# esp32-4-channel.net
KiCad netlist of a schematic drawn in EasyEDA
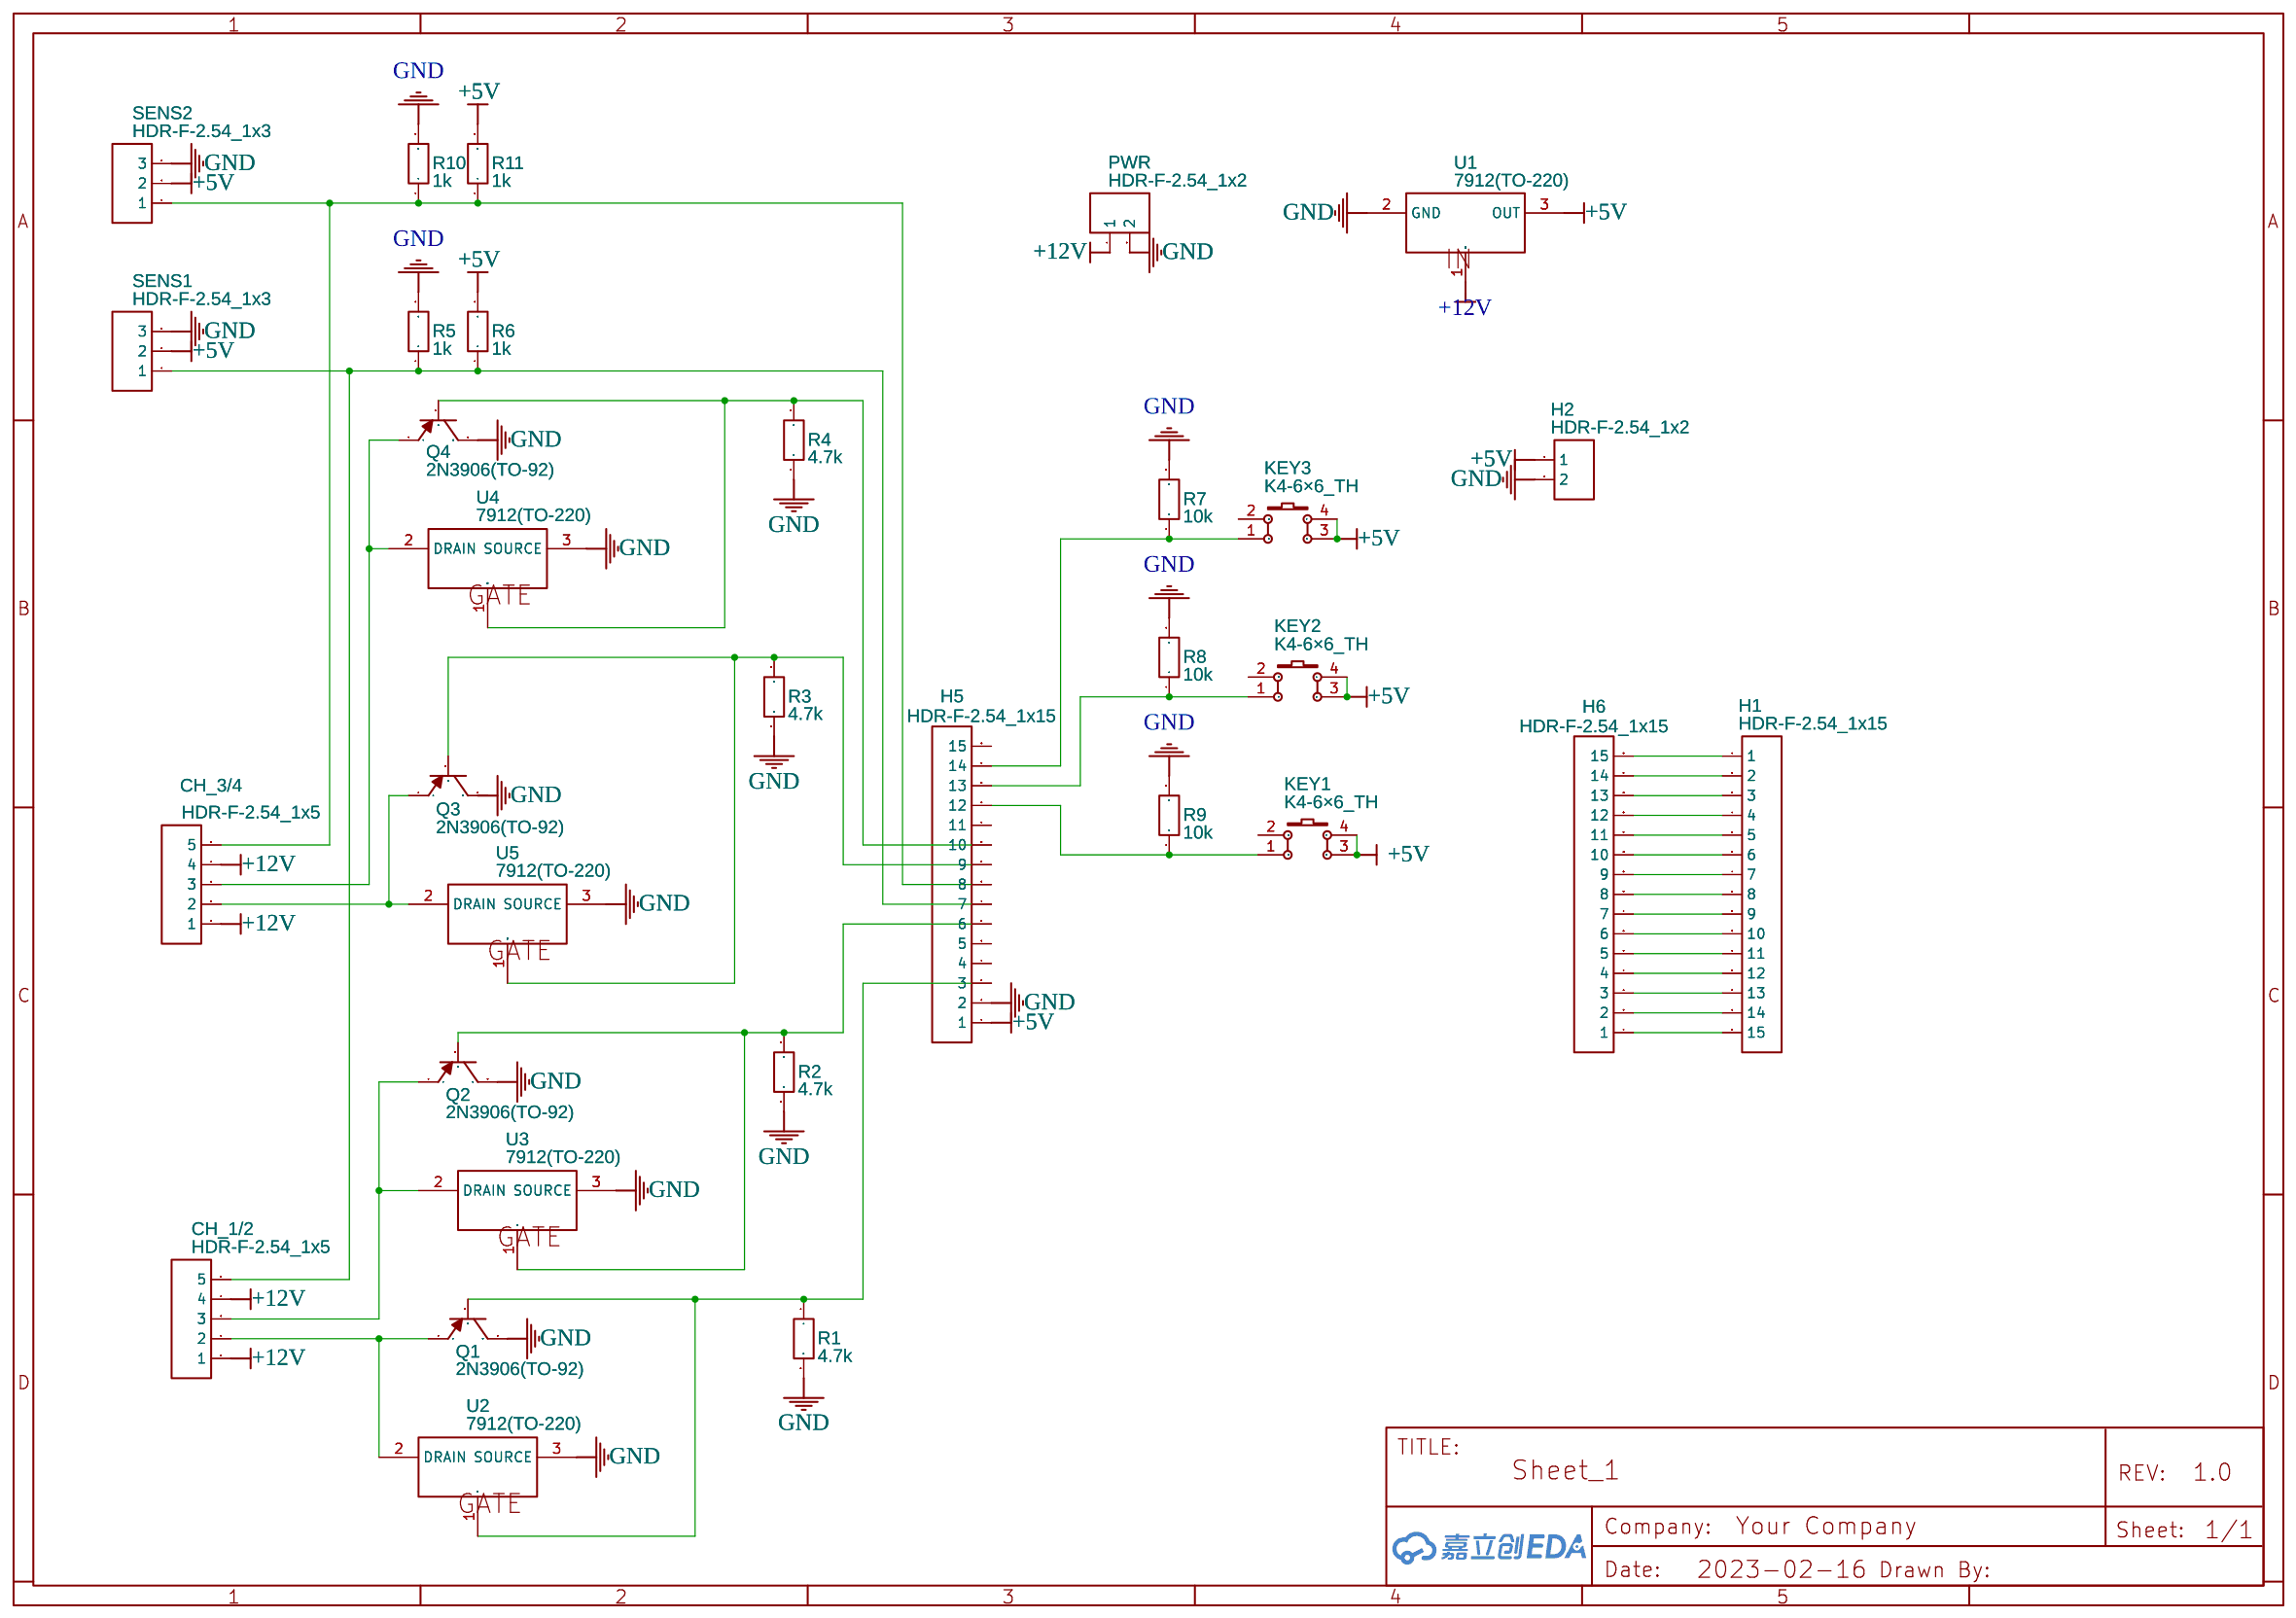
[diagram p0: schematic sheet]

(export (version "E")
  (design (tool "Eeschema 10.0.6"))
  (components
    (comp (ref "CH_1/2")
      (value "HDR-F-2.54_1x5")
      (fields (field (name "BOM_Supplier Part") "C50950"))
      (libsource (lib "") (part "HDR-F-2.54_1x5_1"))
    )
    (comp (ref "CH_3/4")
      (value "HDR-F-2.54_1x5")
      (fields (field (name "BOM_Supplier Part") "C50950"))
      (libsource (lib "") (part "HDR-F-2.54_1x5"))
    )
    (comp (ref "H1")
      (value "HDR-F-2.54_1x15")
      (fields (field (name "BOM_Supplier Part") "C124408"))
      (libsource (lib "") (part "HDR-F-2.54_1x15_1"))
    )
    (comp (ref "H2")
      (value "HDR-F-2.54_1x2")
      (fields (field (name "BOM_Supplier Part") "C49661"))
      (libsource (lib "") (part "HDR-F-2.54_1x2_1"))
    )
    (comp (ref "H5")
      (value "HDR-F-2.54_1x15")
      (fields (field (name "BOM_Supplier Part") "C124408"))
      (libsource (lib "") (part "HDR-F-2.54_1x15"))
    )
    (comp (ref "H6")
      (value "HDR-F-2.54_1x15")
      (fields (field (name "BOM_Supplier Part") "C124408"))
      (libsource (lib "") (part "HDR-F-2.54_1x15"))
    )
    (comp (ref "KEY1")
      (value "K4-6×6_TH")
      (fields
        (field (name "BOM_Manufacturer Part") "K2-1102DP-E4SW-04")
        (field (name "BOM_Supplier Part") "C136684")
      )
      (libsource (lib "") (part "K4-6×6_TH"))
    )
    (comp (ref "KEY2")
      (value "K4-6×6_TH")
      (fields
        (field (name "BOM_Manufacturer Part") "K2-1102DP-E4SW-04")
        (field (name "BOM_Supplier Part") "C136684")
      )
      (libsource (lib "") (part "K4-6×6_TH"))
    )
    (comp (ref "KEY3")
      (value "K4-6×6_TH")
      (fields
        (field (name "BOM_Manufacturer Part") "K2-1102DP-E4SW-04")
        (field (name "BOM_Supplier Part") "C136684")
      )
      (libsource (lib "") (part "K4-6×6_TH"))
    )
    (comp (ref "PWR")
      (value "HDR-F-2.54_1x2")
      (fields (field (name "BOM_Supplier Part") "C49661"))
      (libsource (lib "") (part "HDR-F-2.54_1x2"))
    )
    (comp (ref "Q1")
      (value "2N3906(TO-92)")
      (fields (field (name "BOM_Manufacturer Part") "2N3906") (field (name "BOM_Supplier Part") "C9809"))
      (libsource (lib "") (part "2N3906(TO-92)"))
    )
    (comp (ref "Q2")
      (value "2N3906(TO-92)")
      (fields (field (name "BOM_Manufacturer Part") "2N3906") (field (name "BOM_Supplier Part") "C9809"))
      (libsource (lib "") (part "2N3906(TO-92)"))
    )
    (comp (ref "Q3")
      (value "2N3906(TO-92)")
      (fields (field (name "BOM_Manufacturer Part") "2N3906") (field (name "BOM_Supplier Part") "C9809"))
      (libsource (lib "") (part "2N3906(TO-92)"))
    )
    (comp (ref "Q4")
      (value "2N3906(TO-92)")
      (fields (field (name "BOM_Manufacturer Part") "2N3906") (field (name "BOM_Supplier Part") "C9809"))
      (libsource (lib "") (part "2N3906(TO-92)"))
    )
    (comp (ref "R1") (value "4.7k") (libsource (lib "") (part "R_AXIAL-0.3_EU_1")))
    (comp (ref "R2") (value "4.7k") (libsource (lib "") (part "R_AXIAL-0.3_EU")))
    (comp (ref "R3") (value "4.7k") (libsource (lib "") (part "R_AXIAL-0.3_EU")))
    (comp (ref "R4") (value "4.7k") (libsource (lib "") (part "R_AXIAL-0.3_EU")))
    (comp (ref "R5") (value "1k") (libsource (lib "") (part "R_AXIAL-0.3_EU")))
    (comp (ref "R6") (value "1k") (libsource (lib "") (part "R_AXIAL-0.3_EU")))
    (comp (ref "R7") (value "10k") (libsource (lib "") (part "R_AXIAL-0.3_EU")))
    (comp (ref "R8") (value "10k") (libsource (lib "") (part "R_AXIAL-0.3_EU")))
    (comp (ref "R9") (value "10k") (libsource (lib "") (part "R_AXIAL-0.3_EU")))
    (comp (ref "R10") (value "1k") (libsource (lib "") (part "R_AXIAL-0.3_EU")))
    (comp (ref "R11") (value "1k") (libsource (lib "") (part "R_AXIAL-0.3_EU")))
    (comp (ref "SENS1")
      (value "HDR-F-2.54_1x3")
      (fields (field (name "BOM_Supplier Part") "C146690"))
      (libsource (lib "") (part "HDR-F-2.54_1x3"))
    )
    (comp (ref "SENS2")
      (value "HDR-F-2.54_1x3")
      (fields (field (name "BOM_Supplier Part") "C146690"))
      (libsource (lib "") (part "HDR-F-2.54_1x3"))
    )
    (comp (ref "U1")
      (value "7912(TO-220)")
      (fields (field (name "BOM_Manufacturer Part") "L7912CV-DG") (field (name "BOM_Supplier Part") "C3797"))
      (libsource (lib "") (part "7912(TO-220)_1"))
    )
    (comp (ref "U2")
      (value "7912(TO-220)")
      (fields (field (name "BOM_Manufacturer Part") "L7912CV-DG") (field (name "BOM_Supplier Part") "C3797"))
      (libsource (lib "") (part "7912(TO-220)"))
    )
    (comp (ref "U3")
      (value "7912(TO-220)")
      (fields (field (name "BOM_Manufacturer Part") "L7912CV-DG") (field (name "BOM_Supplier Part") "C3797"))
      (libsource (lib "") (part "7912(TO-220)"))
    )
    (comp (ref "U4")
      (value "7912(TO-220)")
      (fields (field (name "BOM_Manufacturer Part") "L7912CV-DG") (field (name "BOM_Supplier Part") "C3797"))
      (libsource (lib "") (part "7912(TO-220)"))
    )
    (comp (ref "U5")
      (value "7912(TO-220)")
      (fields (field (name "BOM_Manufacturer Part") "L7912CV-DG") (field (name "BOM_Supplier Part") "C3797"))
      (libsource (lib "") (part "7912(TO-220)"))
    )
  )
  (nets
    (net (code "1") (name "+5V") (class "Default")
      (node (ref "H2") (pin "1") (pinfunction "1_1") (pintype "input"))
      (node (ref "H5") (pin "1") (pinfunction "1_1") (pintype "unspecified"))
      (node (ref "KEY1") (pin "3") (pinfunction "3_3") (pintype "unspecified"))
      (node (ref "KEY1") (pin "4") (pinfunction "4_4") (pintype "unspecified"))
      (node (ref "KEY2") (pin "3") (pinfunction "3_3") (pintype "unspecified"))
      (node (ref "KEY2") (pin "4") (pinfunction "4_4") (pintype "unspecified"))
      (node (ref "KEY3") (pin "3") (pinfunction "3_3") (pintype "unspecified"))
      (node (ref "KEY3") (pin "4") (pinfunction "4_4") (pintype "unspecified"))
      (node (ref "R11") (pin "2") (pinfunction "2_2") (pintype "unspecified"))
      (node (ref "R6") (pin "2") (pinfunction "2_2") (pintype "unspecified"))
      (node (ref "SENS1") (pin "2") (pinfunction "2_2") (pintype "input"))
      (node (ref "SENS2") (pin "2") (pinfunction "2_2") (pintype "input"))
      (node (ref "U1") (pin "3") (pinfunction "OUT_3") (pintype "passive"))
    )
    (net (code "2") (name "+12V") (class "Default")
      (node (ref "CH_1/2") (pin "1") (pinfunction "1_1") (pintype "unspecified"))
      (node (ref "CH_1/2") (pin "4") (pinfunction "4_4") (pintype "unspecified"))
      (node (ref "CH_3/4") (pin "1") (pinfunction "1_1") (pintype "unspecified"))
      (node (ref "CH_3/4") (pin "4") (pinfunction "4_4") (pintype "unspecified"))
      (node (ref "PWR") (pin "1") (pinfunction "1_1") (pintype "input"))
      (node (ref "U1") (pin "1") (pinfunction "GND_1") (pintype "passive"))
    )
    (net (code "3") (name "GND") (class "Default")
      (node (ref "H2") (pin "2") (pinfunction "2_2") (pintype "input"))
      (node (ref "H5") (pin "2") (pinfunction "2_2") (pintype "unspecified"))
      (node (ref "PWR") (pin "2") (pinfunction "2_2") (pintype "input"))
      (node (ref "Q1") (pin "3") (pinfunction "C_3") (pintype "input"))
      (node (ref "Q2") (pin "3") (pinfunction "C_3") (pintype "input"))
      (node (ref "Q3") (pin "3") (pinfunction "C_3") (pintype "input"))
      (node (ref "Q4") (pin "3") (pinfunction "C_3") (pintype "input"))
      (node (ref "R1") (pin "2") (pinfunction "2_2") (pintype "unspecified"))
      (node (ref "R10") (pin "2") (pinfunction "2_2") (pintype "unspecified"))
      (node (ref "R2") (pin "1") (pinfunction "1_1") (pintype "unspecified"))
      (node (ref "R3") (pin "1") (pinfunction "1_1") (pintype "unspecified"))
      (node (ref "R4") (pin "1") (pinfunction "1_1") (pintype "unspecified"))
      (node (ref "R5") (pin "2") (pinfunction "2_2") (pintype "unspecified"))
      (node (ref "R7") (pin "2") (pinfunction "2_2") (pintype "unspecified"))
      (node (ref "R8") (pin "2") (pinfunction "2_2") (pintype "unspecified"))
      (node (ref "R9") (pin "2") (pinfunction "2_2") (pintype "unspecified"))
      (node (ref "SENS1") (pin "3") (pinfunction "3_3") (pintype "input"))
      (node (ref "SENS2") (pin "3") (pinfunction "3_3") (pintype "input"))
      (node (ref "U1") (pin "2") (pinfunction "GND_2") (pintype "passive"))
      (node (ref "U2") (pin "3") (pinfunction "SOURCE_3") (pintype "passive"))
      (node (ref "U3") (pin "3") (pinfunction "SOURCE_3") (pintype "passive"))
      (node (ref "U4") (pin "3") (pinfunction "SOURCE_3") (pintype "passive"))
      (node (ref "U5") (pin "3") (pinfunction "SOURCE_3") (pintype "passive"))
    )
    (net (code "4") (name "Net-(CH_1/2-Pad5)") (class "Default")
      (node (ref "CH_1/2") (pin "5") (pinfunction "5_5") (pintype "unspecified"))
      (node (ref "H5") (pin "7") (pinfunction "7_7") (pintype "unspecified"))
      (node (ref "R5") (pin "1") (pinfunction "1_1") (pintype "unspecified"))
      (node (ref "R6") (pin "1") (pinfunction "1_1") (pintype "unspecified"))
      (node (ref "SENS1") (pin "1") (pinfunction "1_1") (pintype "input"))
    )
    (net (code "5") (name "Net-(CH_3/4-Pad5)") (class "Default")
      (node (ref "CH_3/4") (pin "5") (pinfunction "5_5") (pintype "unspecified"))
      (node (ref "H5") (pin "8") (pinfunction "8_8") (pintype "unspecified"))
      (node (ref "R10") (pin "1") (pinfunction "1_1") (pintype "unspecified"))
      (node (ref "R11") (pin "1") (pinfunction "1_1") (pintype "unspecified"))
      (node (ref "SENS2") (pin "1") (pinfunction "1_1") (pintype "input"))
    )
    (net (code "6") (name "Net-(H1-Pad1)") (class "Default")
      (node (ref "H1") (pin "1") (pinfunction "1_1") (pintype "unspecified"))
      (node (ref "H6") (pin "15") (pinfunction "15_15") (pintype "unspecified"))
    )
    (net (code "7") (name "Net-(H1-Pad2)") (class "Default")
      (node (ref "H1") (pin "2") (pinfunction "2_2") (pintype "unspecified"))
      (node (ref "H6") (pin "14") (pinfunction "14_14") (pintype "unspecified"))
    )
    (net (code "8") (name "Net-(H1-Pad3)") (class "Default")
      (node (ref "H1") (pin "3") (pinfunction "3_3") (pintype "unspecified"))
      (node (ref "H6") (pin "13") (pinfunction "13_13") (pintype "unspecified"))
    )
    (net (code "9") (name "Net-(H1-Pad4)") (class "Default")
      (node (ref "H1") (pin "4") (pinfunction "4_4") (pintype "unspecified"))
      (node (ref "H6") (pin "12") (pinfunction "12_12") (pintype "unspecified"))
    )
    (net (code "10") (name "Net-(H1-Pad5)") (class "Default")
      (node (ref "H1") (pin "5") (pinfunction "5_5") (pintype "unspecified"))
      (node (ref "H6") (pin "11") (pinfunction "11_11") (pintype "unspecified"))
    )
    (net (code "11") (name "Net-(H1-Pad6)") (class "Default")
      (node (ref "H1") (pin "6") (pinfunction "6_6") (pintype "unspecified"))
      (node (ref "H6") (pin "10") (pinfunction "10_10") (pintype "unspecified"))
    )
    (net (code "12") (name "Net-(H1-Pad7)") (class "Default")
      (node (ref "H1") (pin "7") (pinfunction "7_7") (pintype "unspecified"))
      (node (ref "H6") (pin "9") (pinfunction "9_9") (pintype "unspecified"))
    )
    (net (code "13") (name "Net-(H1-Pad8)") (class "Default")
      (node (ref "H1") (pin "8") (pinfunction "8_8") (pintype "unspecified"))
      (node (ref "H6") (pin "8") (pinfunction "8_8") (pintype "unspecified"))
    )
    (net (code "14") (name "Net-(H1-Pad9)") (class "Default")
      (node (ref "H1") (pin "9") (pinfunction "9_9") (pintype "unspecified"))
      (node (ref "H6") (pin "7") (pinfunction "7_7") (pintype "unspecified"))
    )
    (net (code "15") (name "Net-(H1-Pad10)") (class "Default")
      (node (ref "H1") (pin "10") (pinfunction "10_10") (pintype "unspecified"))
      (node (ref "H6") (pin "6") (pinfunction "6_6") (pintype "unspecified"))
    )
    (net (code "16") (name "Net-(H1-Pad11)") (class "Default")
      (node (ref "H1") (pin "11") (pinfunction "11_11") (pintype "unspecified"))
      (node (ref "H6") (pin "5") (pinfunction "5_5") (pintype "unspecified"))
    )
    (net (code "17") (name "Net-(H1-Pad12)") (class "Default")
      (node (ref "H1") (pin "12") (pinfunction "12_12") (pintype "unspecified"))
      (node (ref "H6") (pin "4") (pinfunction "4_4") (pintype "unspecified"))
    )
    (net (code "18") (name "Net-(H1-Pad13)") (class "Default")
      (node (ref "H1") (pin "13") (pinfunction "13_13") (pintype "unspecified"))
      (node (ref "H6") (pin "3") (pinfunction "3_3") (pintype "unspecified"))
    )
    (net (code "19") (name "Net-(H1-Pad14)") (class "Default")
      (node (ref "H1") (pin "14") (pinfunction "14_14") (pintype "unspecified"))
      (node (ref "H6") (pin "2") (pinfunction "2_2") (pintype "unspecified"))
    )
    (net (code "20") (name "Net-(H1-Pad15)") (class "Default")
      (node (ref "H1") (pin "15") (pinfunction "15_15") (pintype "unspecified"))
      (node (ref "H6") (pin "1") (pinfunction "1_1") (pintype "unspecified"))
    )
    (net (code "21") (name "Net-(H5-Pad12)") (class "Default")
      (node (ref "H5") (pin "12") (pinfunction "12_12") (pintype "unspecified"))
      (node (ref "KEY1") (pin "1") (pinfunction "1_1") (pintype "unspecified"))
      (node (ref "R9") (pin "1") (pinfunction "1_1") (pintype "unspecified"))
    )
    (net (code "22") (name "Net-(H5-Pad13)") (class "Default")
      (node (ref "H5") (pin "13") (pinfunction "13_13") (pintype "unspecified"))
      (node (ref "KEY2") (pin "1") (pinfunction "1_1") (pintype "unspecified"))
      (node (ref "R8") (pin "1") (pinfunction "1_1") (pintype "unspecified"))
    )
    (net (code "23") (name "Net-(H5-Pad14)") (class "Default")
      (node (ref "H5") (pin "14") (pinfunction "14_14") (pintype "unspecified"))
      (node (ref "KEY3") (pin "1") (pinfunction "1_1") (pintype "unspecified"))
      (node (ref "R7") (pin "1") (pinfunction "1_1") (pintype "unspecified"))
    )
    (net (code "24") (name "Net-(Q1-B)") (class "Default")
      (node (ref "H5") (pin "3") (pinfunction "3_3") (pintype "unspecified"))
      (node (ref "Q1") (pin "2") (pinfunction "B_2") (pintype "input"))
      (node (ref "R1") (pin "1") (pinfunction "1_1") (pintype "unspecified"))
      (node (ref "U2") (pin "1") (pinfunction "GND_1") (pintype "passive"))
    )
    (net (code "25") (name "Net-(Q1-E)") (class "Default")
      (node (ref "CH_1/2") (pin "2") (pinfunction "2_2") (pintype "unspecified"))
      (node (ref "Q1") (pin "1") (pinfunction "E_1") (pintype "input"))
      (node (ref "U2") (pin "2") (pinfunction "DRAIN_2") (pintype "passive"))
    )
    (net (code "26") (name "Net-(Q2-B)") (class "Default")
      (node (ref "H5") (pin "6") (pinfunction "6_6") (pintype "unspecified"))
      (node (ref "Q2") (pin "2") (pinfunction "B_2") (pintype "input"))
      (node (ref "R2") (pin "2") (pinfunction "2_2") (pintype "unspecified"))
      (node (ref "U3") (pin "1") (pinfunction "GND_1") (pintype "passive"))
    )
    (net (code "27") (name "Net-(Q2-E)") (class "Default")
      (node (ref "CH_1/2") (pin "3") (pinfunction "3_3") (pintype "unspecified"))
      (node (ref "Q2") (pin "1") (pinfunction "E_1") (pintype "input"))
      (node (ref "U3") (pin "2") (pinfunction "DRAIN_2") (pintype "passive"))
    )
    (net (code "28") (name "Net-(Q3-B)") (class "Default")
      (node (ref "H5") (pin "9") (pinfunction "9_9") (pintype "unspecified"))
      (node (ref "Q3") (pin "2") (pinfunction "B_2") (pintype "input"))
      (node (ref "R3") (pin "2") (pinfunction "2_2") (pintype "unspecified"))
      (node (ref "U5") (pin "1") (pinfunction "GND_1") (pintype "passive"))
    )
    (net (code "29") (name "Net-(Q3-E)") (class "Default")
      (node (ref "CH_3/4") (pin "2") (pinfunction "2_2") (pintype "unspecified"))
      (node (ref "Q3") (pin "1") (pinfunction "E_1") (pintype "input"))
      (node (ref "U5") (pin "2") (pinfunction "DRAIN_2") (pintype "passive"))
    )
    (net (code "30") (name "Net-(Q4-B)") (class "Default")
      (node (ref "H5") (pin "10") (pinfunction "10_10") (pintype "unspecified"))
      (node (ref "Q4") (pin "2") (pinfunction "B_2") (pintype "input"))
      (node (ref "R4") (pin "2") (pinfunction "2_2") (pintype "unspecified"))
      (node (ref "U4") (pin "1") (pinfunction "GND_1") (pintype "passive"))
    )
    (net (code "31") (name "Net-(Q4-E)") (class "Default")
      (node (ref "CH_3/4") (pin "3") (pinfunction "3_3") (pintype "unspecified"))
      (node (ref "Q4") (pin "1") (pinfunction "E_1") (pintype "input"))
      (node (ref "U4") (pin "2") (pinfunction "DRAIN_2") (pintype "passive"))
    )
    (net (code "32") (name "unconnected-(H5-Pad4)") (class "Default")
      (node (ref "H5") (pin "4") (pinfunction "4_4") (pintype "unspecified"))
    )
    (net (code "33") (name "unconnected-(H5-Pad5)") (class "Default")
      (node (ref "H5") (pin "5") (pinfunction "5_5") (pintype "unspecified"))
    )
    (net (code "34") (name "unconnected-(H5-Pad11)") (class "Default")
      (node (ref "H5") (pin "11") (pinfunction "11_11") (pintype "unspecified"))
    )
    (net (code "35") (name "unconnected-(H5-Pad15)") (class "Default")
      (node (ref "H5") (pin "15") (pinfunction "15_15") (pintype "unspecified"))
    )
    (net (code "36") (name "unconnected-(KEY1-Pad2)") (class "Default")
      (node (ref "KEY1") (pin "2") (pinfunction "2_2") (pintype "unspecified"))
    )
    (net (code "37") (name "unconnected-(KEY2-Pad2)") (class "Default")
      (node (ref "KEY2") (pin "2") (pinfunction "2_2") (pintype "unspecified"))
    )
    (net (code "38") (name "unconnected-(KEY3-Pad2)") (class "Default")
      (node (ref "KEY3") (pin "2") (pinfunction "2_2") (pintype "unspecified"))
    )
  )
)
